# calibration-thru-reflect-match-sma.net
KiCad netlist of a schematic drawn in EAGLE
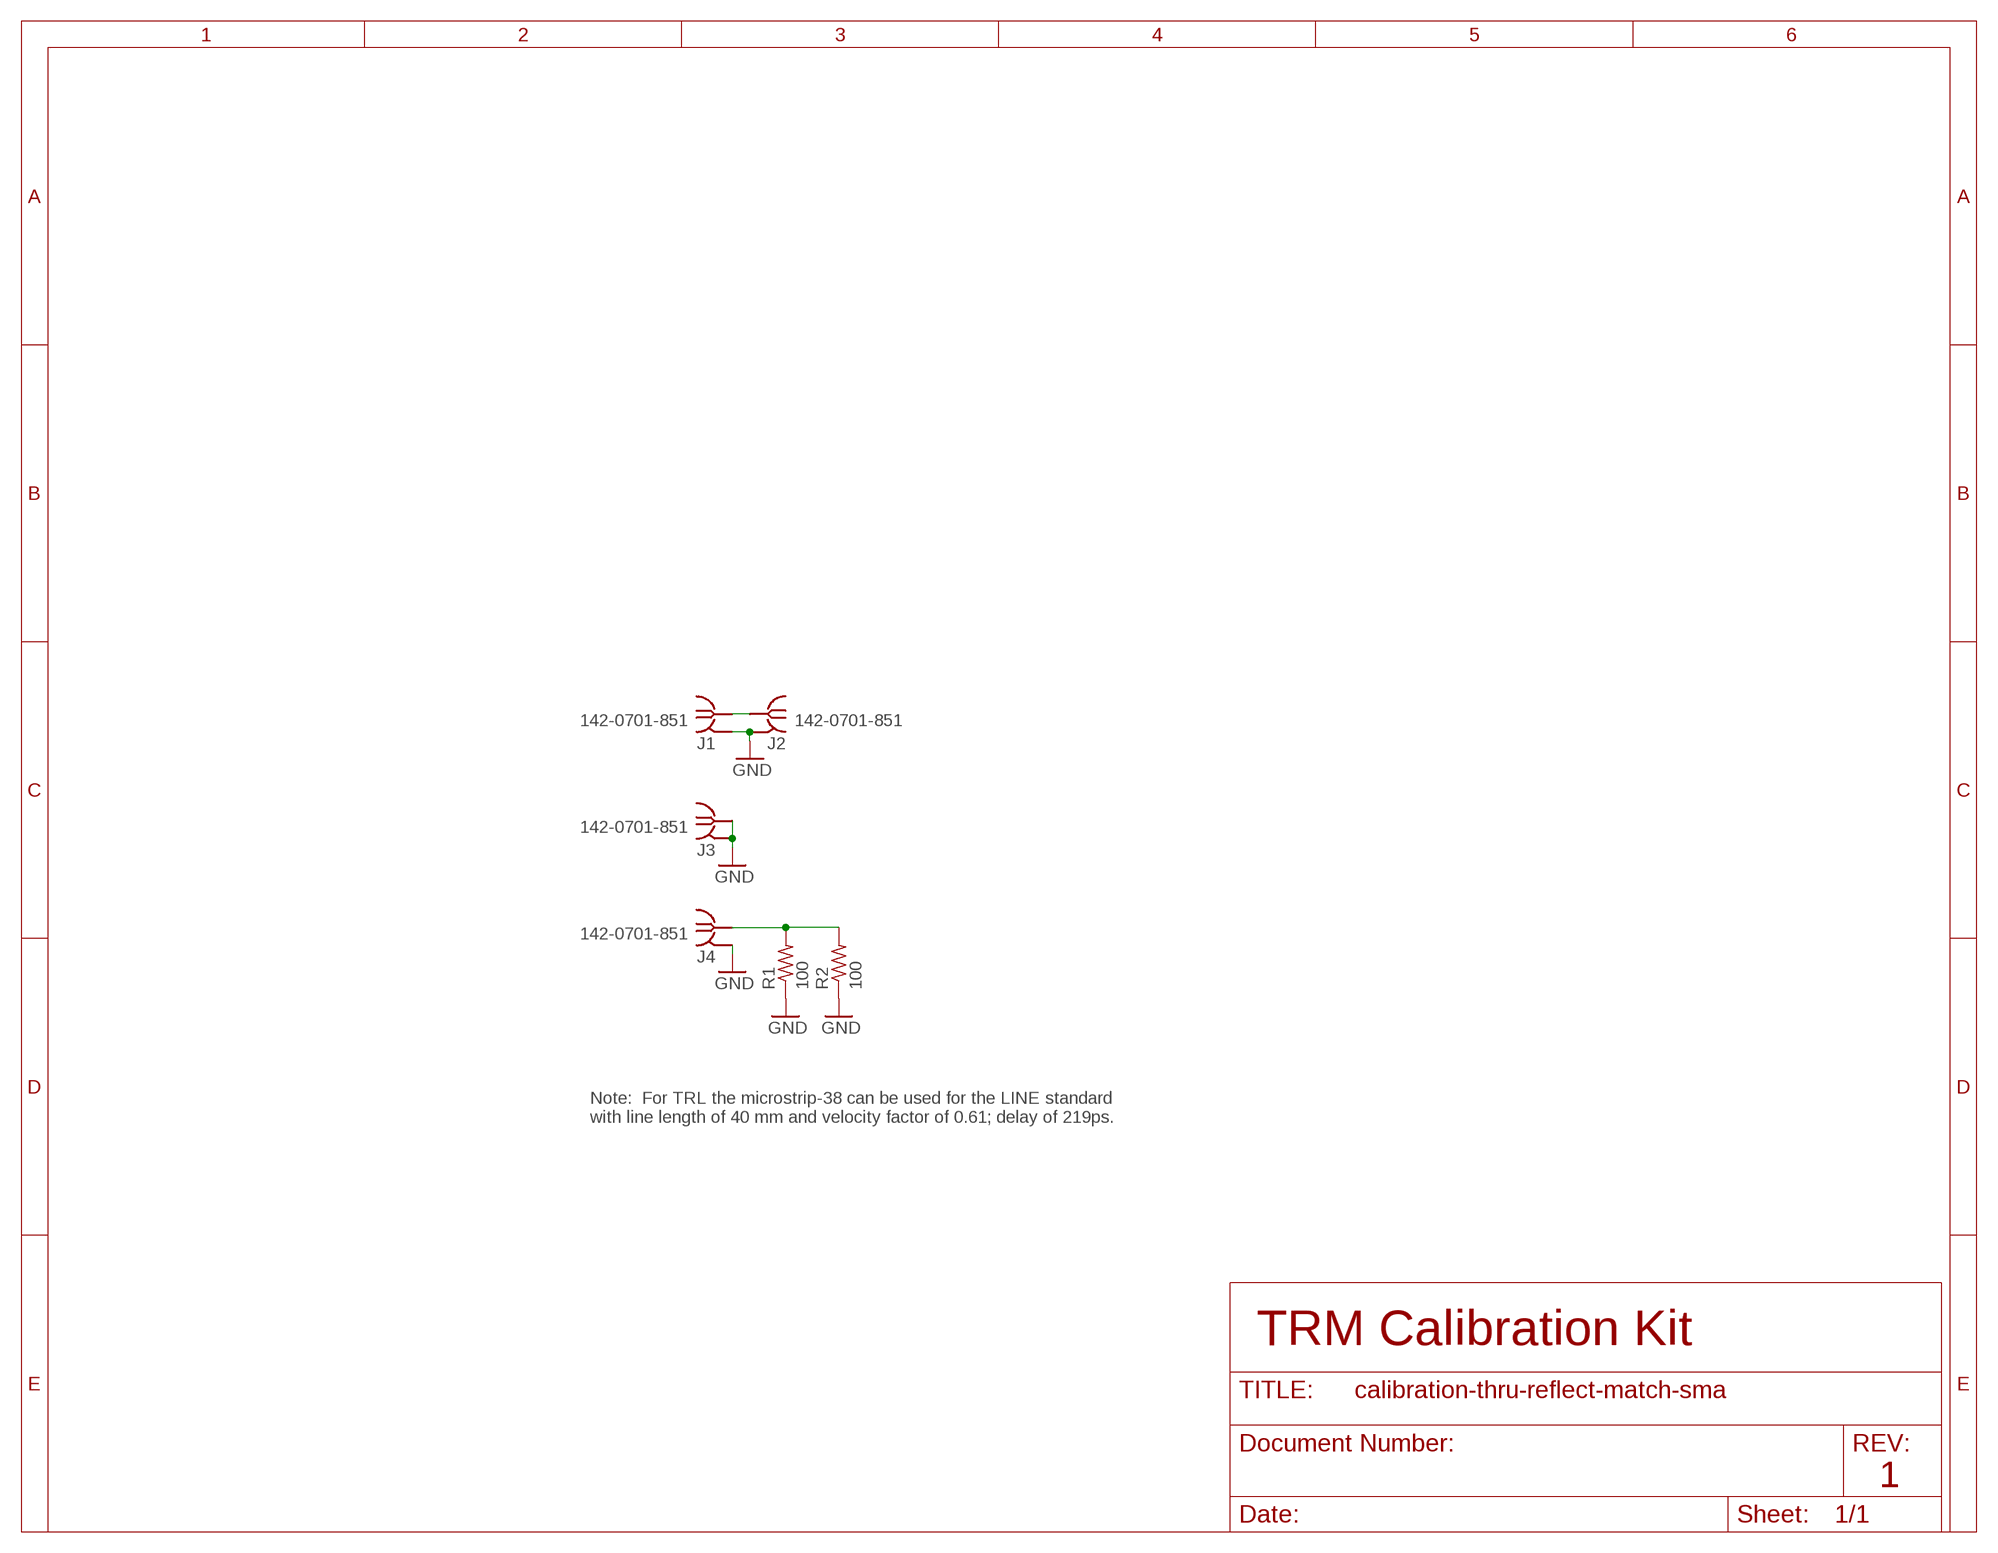
[diagram p0: schematic, sheet 1]

(export (version "E")
  (design (tool "Eeschema 10.0.6"))
  (components
    (comp (ref "J1")
      (value "142-0701-851")
      (footprint "eagle-import:142-0701-851")
      (libsource (lib "eagle-import") (part "142-0701-851"))
    )
    (comp (ref "J2")
      (value "142-0701-851")
      (footprint "eagle-import:142-0701-851")
      (libsource (lib "eagle-import") (part "142-0701-851"))
    )
    (comp (ref "J3")
      (value "142-0701-851")
      (footprint "eagle-import:142-0701-851")
      (libsource (lib "eagle-import") (part "142-0701-851"))
    )
    (comp (ref "J4")
      (value "142-0701-851")
      (footprint "eagle-import:142-0701-851")
      (libsource (lib "eagle-import") (part "142-0701-851"))
    )
    (comp (ref "R1")
      (value "100")
      (footprint "eagle-import:.0402-C-NOSILK")
      (libsource (lib "eagle-import") (part "R-US_0402-C-NOSILK"))
    )
    (comp (ref "R2")
      (value "100")
      (footprint "eagle-import:.0402-C-NOSILK")
      (libsource (lib "eagle-import") (part "R-US_0402-C-NOSILK"))
    )
  )
  (nets
    (net (code "1") (name "GND") (class "Default")
      (node (ref "J1") (pin "GND1") (pinfunction "GND_GND1") (pintype "bidirectional"))
      (node (ref "J1") (pin "GND2") (pinfunction "GND_GND2") (pintype "bidirectional"))
      (node (ref "J1") (pin "GND3") (pinfunction "GND_GND3") (pintype "bidirectional"))
      (node (ref "J1") (pin "GND4") (pinfunction "GND_GND4") (pintype "bidirectional"))
      (node (ref "J2") (pin "GND1") (pinfunction "GND_GND1") (pintype "bidirectional"))
      (node (ref "J2") (pin "GND2") (pinfunction "GND_GND2") (pintype "bidirectional"))
      (node (ref "J2") (pin "GND3") (pinfunction "GND_GND3") (pintype "bidirectional"))
      (node (ref "J2") (pin "GND4") (pinfunction "GND_GND4") (pintype "bidirectional"))
      (node (ref "J3") (pin "GND1") (pinfunction "GND_GND1") (pintype "bidirectional"))
      (node (ref "J3") (pin "GND2") (pinfunction "GND_GND2") (pintype "bidirectional"))
      (node (ref "J3") (pin "GND3") (pinfunction "GND_GND3") (pintype "bidirectional"))
      (node (ref "J3") (pin "GND4") (pinfunction "GND_GND4") (pintype "bidirectional"))
      (node (ref "J3") (pin "RF1") (pinfunction "RF_RF1") (pintype "bidirectional"))
      (node (ref "J4") (pin "GND1") (pinfunction "GND_GND1") (pintype "bidirectional"))
      (node (ref "J4") (pin "GND2") (pinfunction "GND_GND2") (pintype "bidirectional"))
      (node (ref "J4") (pin "GND3") (pinfunction "GND_GND3") (pintype "bidirectional"))
      (node (ref "J4") (pin "GND4") (pinfunction "GND_GND4") (pintype "bidirectional"))
      (node (ref "R1") (pin "1") (pinfunction "1_1") (pintype "passive"))
      (node (ref "R2") (pin "1") (pinfunction "1_1") (pintype "passive"))
    )
    (net (code "2") (name "Net-(J1-RF)") (class "Default")
      (node (ref "J1") (pin "RF1") (pinfunction "RF_RF1") (pintype "bidirectional"))
      (node (ref "J2") (pin "RF1") (pinfunction "RF_RF1") (pintype "bidirectional"))
    )
    (net (code "3") (name "Net-(J4-RF)") (class "Default")
      (node (ref "J4") (pin "RF1") (pinfunction "RF_RF1") (pintype "bidirectional"))
      (node (ref "R1") (pin "2") (pinfunction "2_2") (pintype "passive"))
      (node (ref "R2") (pin "2") (pinfunction "2_2") (pintype "passive"))
    )
  )
)
